# Sheet1.net
KiCad netlist of a schematic drawn in Altium Designer
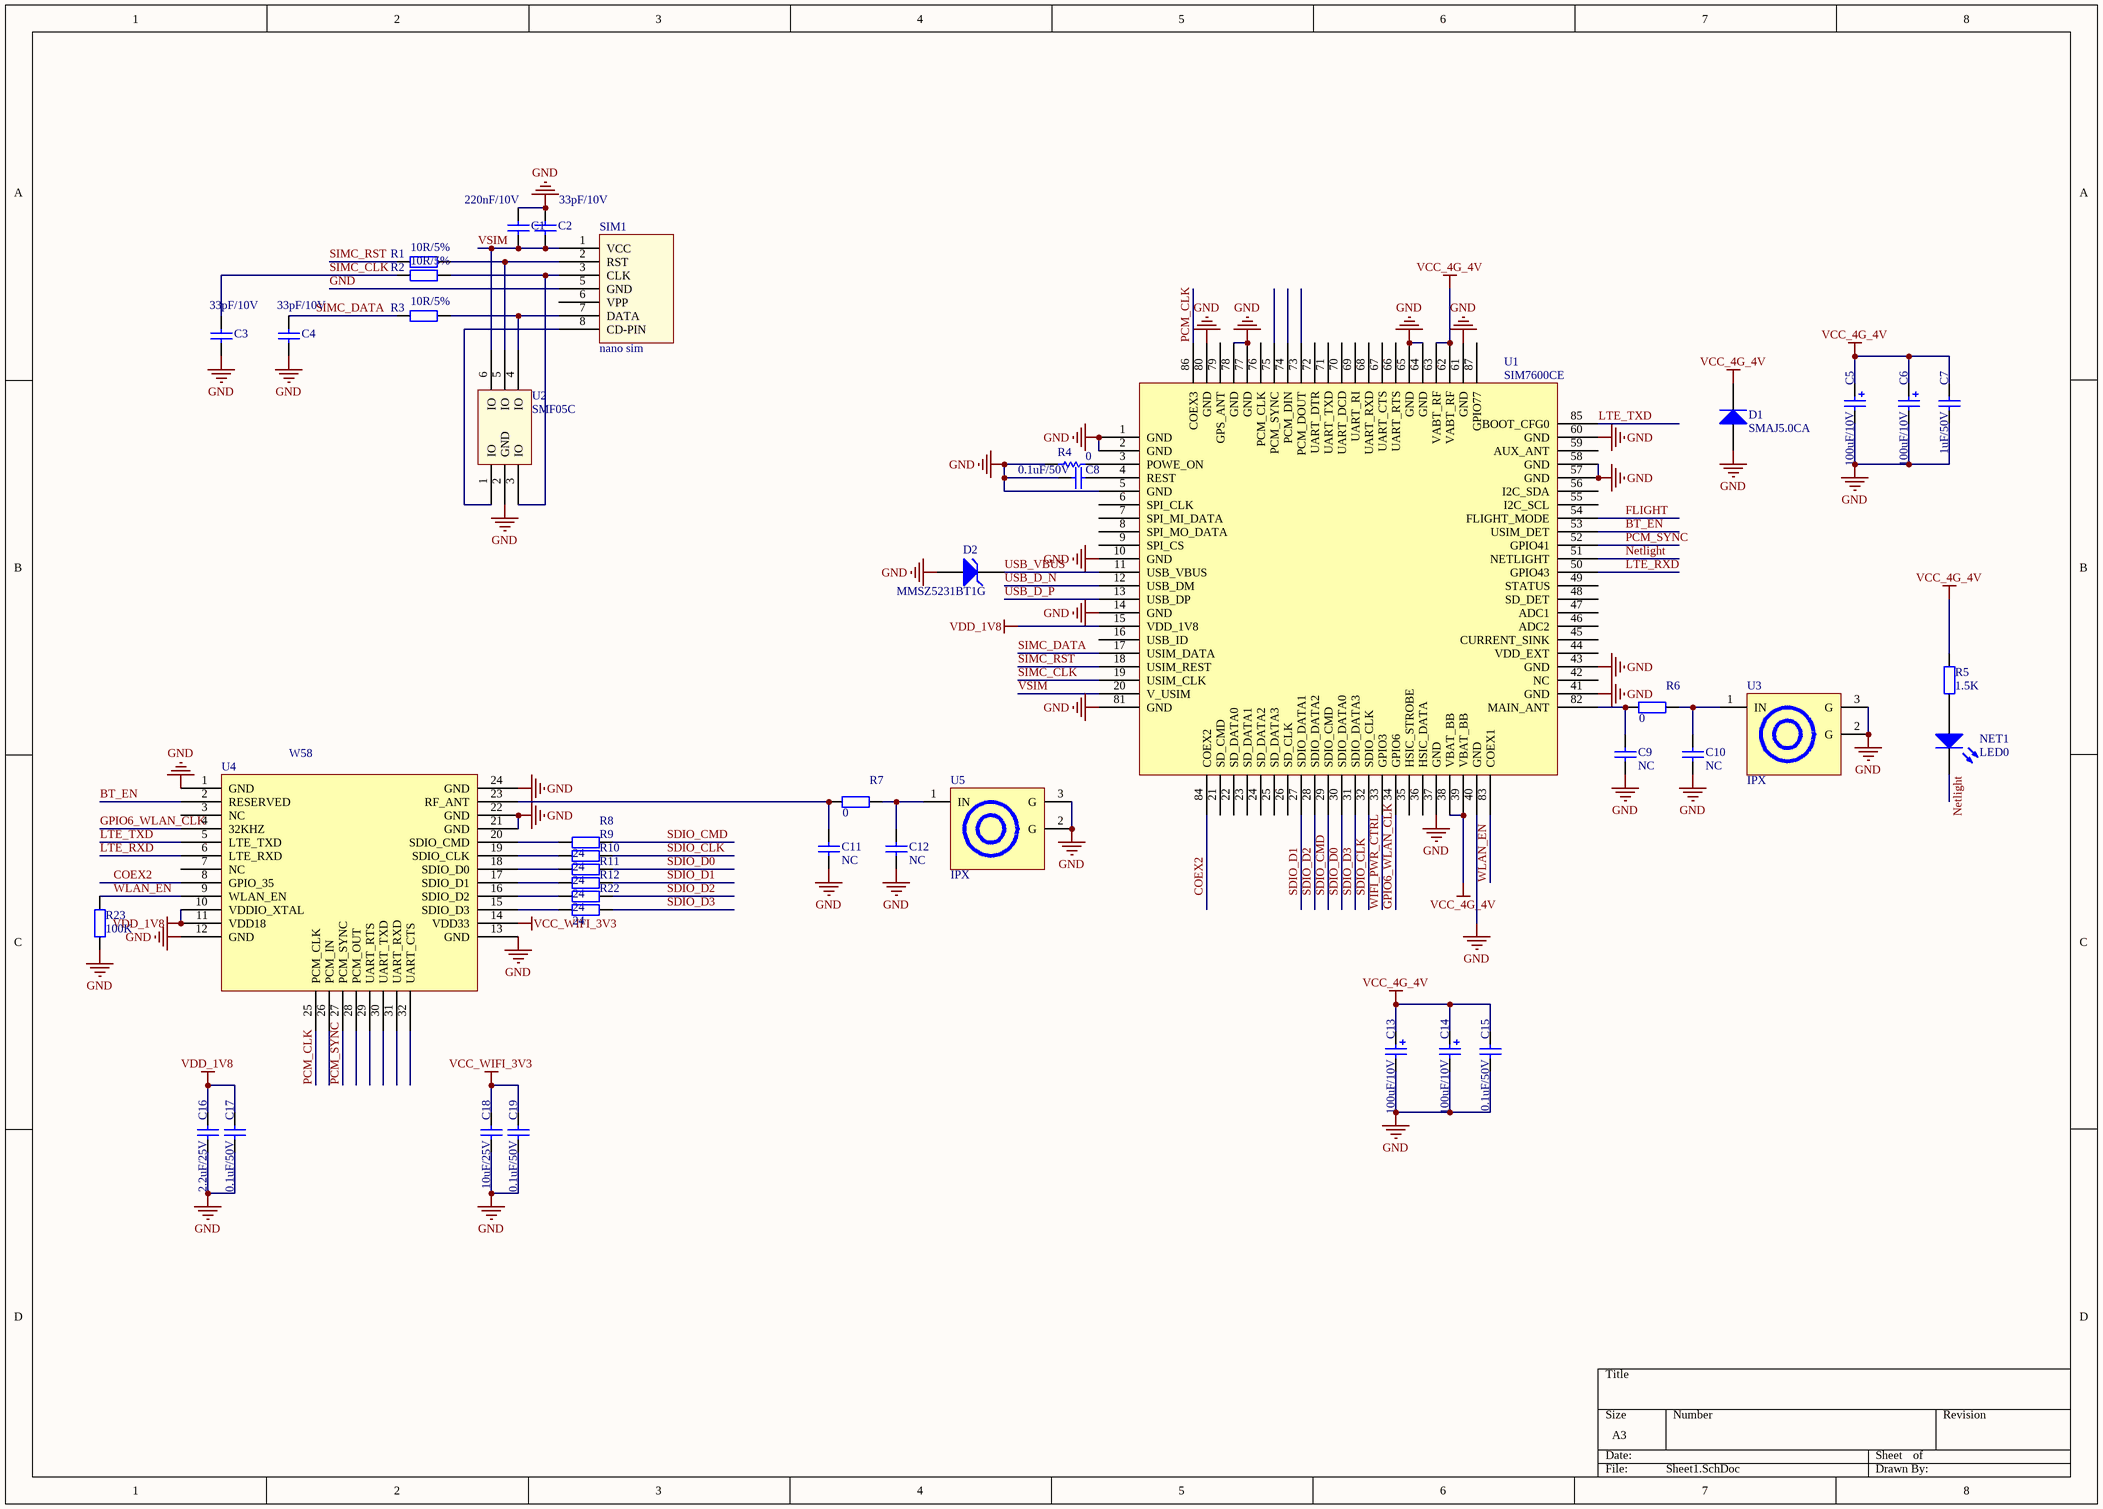
[diagram p0: Sheet1.SchDoc]

(export (version "E")
  (design (tool "Eeschema 10.0.6"))
  (components
    (comp (ref "C1")
      (value "220nF/10V")
      (footprint "C0402")
      (description "Capacitor")
      (fields (field (name "PUBLISHER") "Altium Limited"))
      (libsource (lib "Miscellaneous Devices") (part "Cap"))
    )
    (comp (ref "C2")
      (value "33pF/10V")
      (footprint "C0402")
      (description "Capacitor")
      (fields (field (name "PUBLISHER") "Altium Limited"))
      (libsource (lib "Miscellaneous Devices") (part "Cap"))
    )
    (comp (ref "C3")
      (value "33pF/10V")
      (footprint "C0402")
      (description "Capacitor")
      (fields (field (name "PUBLISHER") "Altium Limited"))
      (libsource (lib "Miscellaneous Devices") (part "Cap"))
    )
    (comp (ref "C4")
      (value "33pF/10V")
      (footprint "C0402")
      (description "Capacitor")
      (fields (field (name "PUBLISHER") "Altium Limited"))
      (libsource (lib "Miscellaneous Devices") (part "Cap"))
    )
    (comp (ref "C5")
      (value "100uF/10V")
      (footprint "3528")
      (description "Polarized Capacitor (Axial)")
      (fields (field (name "PUBLISHER") "Altium Limited"))
      (libsource (lib "Miscellaneous Devices") (part "Cap Pol2"))
    )
    (comp (ref "C6")
      (value "100uF/10V")
      (footprint "3528")
      (description "Polarized Capacitor (Axial)")
      (fields (field (name "PUBLISHER") "Altium Limited"))
      (libsource (lib "Miscellaneous Devices") (part "Cap Pol2"))
    )
    (comp (ref "C7")
      (value "1uF/50V")
      (footprint "0402C")
      (description "Capacitor")
      (fields (field (name "PUBLISHER") "Altium Limited"))
      (libsource (lib "Miscellaneous Devices") (part "Cap"))
    )
    (comp (ref "C8")
      (value "0.1uF/50V")
      (footprint "0402C")
      (description "Capacitor")
      (fields (field (name "PUBLISHER") "Altium Limited"))
      (libsource (lib "Miscellaneous Devices") (part "Cap"))
    )
    (comp (ref "C9")
      (value "NC")
      (footprint "0402C")
      (description "Capacitor")
      (fields (field (name "PUBLISHER") "Altium Limited"))
      (libsource (lib "Miscellaneous Devices") (part "Cap"))
    )
    (comp (ref "C10")
      (value "NC")
      (footprint "0402C")
      (description "Capacitor")
      (fields (field (name "PUBLISHER") "Altium Limited"))
      (libsource (lib "Miscellaneous Devices") (part "Cap"))
    )
    (comp (ref "C11")
      (value "NC")
      (footprint "0402C")
      (description "Capacitor")
      (fields (field (name "PUBLISHER") "Altium Limited"))
      (libsource (lib "Miscellaneous Devices") (part "Cap"))
    )
    (comp (ref "C12")
      (value "NC")
      (footprint "0402C")
      (description "Capacitor")
      (fields (field (name "PUBLISHER") "Altium Limited"))
      (libsource (lib "Miscellaneous Devices") (part "Cap"))
    )
    (comp (ref "C13")
      (value "100uF/10V")
      (footprint "3528")
      (description "Polarized Capacitor (Axial)")
      (fields (field (name "PUBLISHER") "Altium Limited"))
      (libsource (lib "Miscellaneous Devices") (part "Cap Pol2"))
    )
    (comp (ref "C14")
      (value "100uF/10V")
      (footprint "3528")
      (description "Polarized Capacitor (Axial)")
      (fields (field (name "PUBLISHER") "Altium Limited"))
      (libsource (lib "Miscellaneous Devices") (part "Cap Pol2"))
    )
    (comp (ref "C15")
      (value "0.1uF/50V")
      (footprint "0402C")
      (description "Capacitor")
      (fields (field (name "PUBLISHER") "Altium Limited"))
      (libsource (lib "Miscellaneous Devices") (part "Cap"))
    )
    (comp (ref "C16")
      (value "2.2uF/25V")
      (footprint "0402C")
      (description "Capacitor")
      (fields (field (name "PUBLISHER") "Altium Limited"))
      (libsource (lib "Miscellaneous Devices") (part "Cap"))
    )
    (comp (ref "C17")
      (value "0.1uF/50V")
      (footprint "0402C")
      (description "Capacitor")
      (fields (field (name "PUBLISHER") "Altium Limited"))
      (libsource (lib "Miscellaneous Devices") (part "Cap"))
    )
    (comp (ref "C18")
      (value "10uF/25V")
      (footprint "0402C")
      (description "Capacitor")
      (fields (field (name "PUBLISHER") "Altium Limited"))
      (libsource (lib "Miscellaneous Devices") (part "Cap"))
    )
    (comp (ref "C19")
      (value "0.1uF/50V")
      (footprint "0402C")
      (description "Capacitor")
      (fields (field (name "PUBLISHER") "Altium Limited"))
      (libsource (lib "Miscellaneous Devices") (part "Cap"))
    )
    (comp (ref "D1")
      (value "SMAJ5.0CA")
      (footprint "SMA")
      (description "Default Diode")
      (fields (field (name "PUBLISHER") "Altium Limited"))
      (libsource (lib "Miscellaneous Devices") (part "Diode"))
    )
    (comp (ref "D2")
      (value "MMSZ5231BT1G")
      (footprint "SOD123")
      (description "Zener Diode")
      (fields (field (name "PUBLISHER") "Altium Limited"))
      (libsource (lib "Miscellaneous Devices") (part "D Zener"))
    )
    (comp (ref "NET1")
      (value "LED0")
      (footprint "0603LED")
      (description "Typical INFRARED GaAs LED")
      (fields (field (name "PUBLISHER") "Altium Limited"))
      (libsource (lib "Miscellaneous Devices") (part "LED0"))
    )
    (comp (ref "R1")
      (value "10R/5%")
      (footprint "0402R")
      (description "Resistor")
      (fields (field (name "PUBLISHER") "Altium Limited"))
      (libsource (lib "Miscellaneous Devices") (part "Res2"))
    )
    (comp (ref "R2")
      (value "10R/5%")
      (footprint "0402R")
      (description "Resistor")
      (fields (field (name "PUBLISHER") "Altium Limited"))
      (libsource (lib "Miscellaneous Devices") (part "Res2"))
    )
    (comp (ref "R3")
      (value "10R/5%")
      (footprint "0402R")
      (description "Resistor")
      (fields (field (name "PUBLISHER") "Altium Limited"))
      (libsource (lib "Miscellaneous Devices") (part "Res2"))
    )
    (comp (ref "R4")
      (value "0")
      (footprint "0603R")
      (description "Resistor")
      (fields (field (name "PUBLISHER") "Altium Limited"))
      (libsource (lib "Miscellaneous Devices") (part "Res1"))
    )
    (comp (ref "R5")
      (value "1.5K")
      (footprint "0402R")
      (description "Resistor")
      (fields (field (name "PUBLISHER") "Altium Limited"))
      (libsource (lib "") (part "Res2_3"))
    )
    (comp (ref "R6")
      (value "0")
      (footprint "0402R")
      (description "Resistor")
      (fields (field (name "PUBLISHER") "Altium Limited"))
      (libsource (lib "") (part "Res2_2"))
    )
    (comp (ref "R7")
      (value "0")
      (footprint "0402R")
      (description "Resistor")
      (fields (field (name "PUBLISHER") "Altium Limited"))
      (libsource (lib "") (part "Res2_2"))
    )
    (comp (ref "R8")
      (value "24")
      (footprint "0402R")
      (description "Resistor")
      (fields (field (name "PUBLISHER") "Altium Limited"))
      (libsource (lib "") (part "Res2_2"))
    )
    (comp (ref "R9")
      (value "24")
      (footprint "0402R")
      (description "Resistor")
      (fields (field (name "PUBLISHER") "Altium Limited"))
      (libsource (lib "") (part "Res2_2"))
    )
    (comp (ref "R10")
      (value "24")
      (footprint "0402R")
      (description "Resistor")
      (fields (field (name "PUBLISHER") "Altium Limited"))
      (libsource (lib "") (part "Res2_2"))
    )
    (comp (ref "R11")
      (value "24")
      (footprint "0402R")
      (description "Resistor")
      (fields (field (name "PUBLISHER") "Altium Limited"))
      (libsource (lib "") (part "Res2_2"))
    )
    (comp (ref "R12")
      (value "24")
      (footprint "0402R")
      (description "Resistor")
      (fields (field (name "PUBLISHER") "Altium Limited"))
      (libsource (lib "") (part "Res2_2"))
    )
    (comp (ref "R22")
      (value "24")
      (footprint "0402R")
      (description "Resistor")
      (fields (field (name "PUBLISHER") "Altium Limited"))
      (libsource (lib "") (part "Res2_2"))
    )
    (comp (ref "R23")
      (value "100K")
      (footprint "0402R")
      (description "Resistor")
      (fields (field (name "PUBLISHER") "Altium Limited"))
      (libsource (lib "") (part "Res2_1"))
    )
    (comp (ref "SIM1") (value "nano sim") (footprint "Nano SIM") (libsource (lib "lm") (part "nano sim")))
    (comp (ref "U1")
      (value "SIM7600CE")
      (footprint "Pcblib_20110825:SIM7600CE")
      (libsource (lib "DTU_20161116_ZM_V1.1") (part "SIM7600CE"))
    )
    (comp (ref "U2") (value "SMF05C") (footprint "SC70-6L") (libsource (lib "lm") (part "SMF05C")))
    (comp (ref "U3")
      (value "IPX")
      (footprint "ECT8180001581")
      (description "MCU")
      (libsource (lib "MCU") (part "IPX"))
    )
    (comp (ref "U4") (value "W58") (footprint "W58") (libsource (lib "DTU_20161116_ZM_V1.1") (part "W58")))
    (comp (ref "U5")
      (value "IPX")
      (footprint "ECT8180001581")
      (description "MCU")
      (libsource (lib "MCU") (part "IPX"))
    )
  )
  (nets
    (net (code "1") (name "/BT_EN") (class "Default")
      (node (ref "U1") (pin "53") (pinfunction "USIM_DET_53") (pintype "passive"))
      (node (ref "U4") (pin "2") (pinfunction "RESERVED_2") (pintype "passive"))
    )
    (net (code "2") (name "/COEX2") (class "Default")
      (node (ref "U1") (pin "84") (pinfunction "COEX2_84") (pintype "passive"))
      (node (ref "U4") (pin "8") (pinfunction "GPIO_35_8") (pintype "passive"))
    )
    (net (code "3") (name "/FLIGHT") (class "Default")
      (node (ref "U1") (pin "54") (pinfunction "FLIGHT_MODE_54") (pintype "passive"))
    )
    (net (code "4") (name "/GPIO6_WLAN_CLK") (class "Default")
      (node (ref "U1") (pin "34") (pinfunction "GPIO6_34") (pintype "passive"))
      (node (ref "U4") (pin "4") (pinfunction "32KHZ_4") (pintype "passive"))
    )
    (net (code "5") (name "/LTE_RXD") (class "Default")
      (node (ref "U1") (pin "50") (pinfunction "GPIO43_50") (pintype "passive"))
      (node (ref "U4") (pin "6") (pinfunction "LTE_RXD_6") (pintype "passive"))
    )
    (net (code "6") (name "/LTE_TXD") (class "Default")
      (node (ref "U1") (pin "85") (pinfunction "BOOT_CFG0_85") (pintype "passive"))
      (node (ref "U4") (pin "5") (pinfunction "LTE_TXD_5") (pintype "passive"))
    )
    (net (code "7") (name "/Netlight") (class "Default")
      (node (ref "NET1") (pin "2") (pinfunction "K_2") (pintype "passive"))
      (node (ref "U1") (pin "51") (pinfunction "NETLIGHT_51") (pintype "passive"))
    )
    (net (code "8") (name "/PCM_CLK") (class "Default")
      (node (ref "U1") (pin "86") (pinfunction "COEX3_86") (pintype "passive"))
      (node (ref "U4") (pin "25") (pinfunction "PCM_CLK_25") (pintype "passive"))
    )
    (net (code "9") (name "/PCM_SYNC") (class "Default")
      (node (ref "U1") (pin "52") (pinfunction "GPIO41_52") (pintype "passive"))
      (node (ref "U4") (pin "27") (pinfunction "PCM_SYNC_27") (pintype "passive"))
    )
    (net (code "10") (name "/SDIO_CLK") (class "Default")
      (node (ref "R9") (pin "2") (pinfunction "2_2") (pintype "passive"))
      (node (ref "U1") (pin "32") (pinfunction "SDIO_CLK_32") (pintype "passive"))
    )
    (net (code "11") (name "/SDIO_CMD") (class "Default")
      (node (ref "R8") (pin "2") (pinfunction "2_2") (pintype "passive"))
      (node (ref "U1") (pin "29") (pinfunction "SDIO_CMD_29") (pintype "passive"))
    )
    (net (code "12") (name "/SDIO_D0") (class "Default")
      (node (ref "R10") (pin "2") (pinfunction "2_2") (pintype "passive"))
      (node (ref "U1") (pin "30") (pinfunction "SDIO_DATA0_30") (pintype "passive"))
    )
    (net (code "13") (name "/SDIO_D1") (class "Default")
      (node (ref "R11") (pin "2") (pinfunction "2_2") (pintype "passive"))
      (node (ref "U1") (pin "27") (pinfunction "SDIO_DATA1_27") (pintype "passive"))
    )
    (net (code "14") (name "/SDIO_D2") (class "Default")
      (node (ref "R12") (pin "2") (pinfunction "2_2") (pintype "passive"))
      (node (ref "U1") (pin "28") (pinfunction "SDIO_DATA2_28") (pintype "passive"))
    )
    (net (code "15") (name "/SDIO_D3") (class "Default")
      (node (ref "R22") (pin "2") (pinfunction "2_2") (pintype "passive"))
      (node (ref "U1") (pin "31") (pinfunction "SDIO_DATA3_31") (pintype "passive"))
    )
    (net (code "16") (name "/SIMC_CLK") (class "Default")
      (node (ref "C3") (pin "1") (pinfunction "1_1") (pintype "passive"))
      (node (ref "R2") (pin "2") (pinfunction "2_2") (pintype "passive"))
      (node (ref "U1") (pin "19") (pinfunction "USIM_CLK_19") (pintype "passive"))
    )
    (net (code "17") (name "/SIMC_DATA") (class "Default")
      (node (ref "C4") (pin "1") (pinfunction "1_1") (pintype "passive"))
      (node (ref "R3") (pin "2") (pinfunction "2_2") (pintype "passive"))
      (node (ref "U1") (pin "17") (pinfunction "USIM_DATA_17") (pintype "passive"))
    )
    (net (code "18") (name "/SIMC_RST") (class "Default")
      (node (ref "R1") (pin "2") (pinfunction "2_2") (pintype "passive"))
      (node (ref "U1") (pin "18") (pinfunction "USIM_REST_18") (pintype "passive"))
    )
    (net (code "19") (name "/USB_D_N") (class "Default")
      (node (ref "U1") (pin "12") (pinfunction "USB_DM_12") (pintype "passive"))
    )
    (net (code "20") (name "/USB_D_P") (class "Default")
      (node (ref "U1") (pin "13") (pinfunction "USB_DP_13") (pintype "passive"))
    )
    (net (code "21") (name "/USB_VBUS") (class "Default")
      (node (ref "D2") (pin "K") (pinfunction "K_K") (pintype "passive"))
      (node (ref "U1") (pin "11") (pinfunction "USB_VBUS_11") (pintype "passive"))
    )
    (net (code "22") (name "/VSIM") (class "Default")
      (node (ref "C1") (pin "2") (pinfunction "2_2") (pintype "passive"))
      (node (ref "C2") (pin "2") (pinfunction "2_2") (pintype "passive"))
      (node (ref "SIM1") (pin "1") (pinfunction "VCC_1") (pintype "passive"))
      (node (ref "U1") (pin "20") (pinfunction "V_USIM_20") (pintype "passive"))
      (node (ref "U2") (pin "6") (pinfunction "IO_6") (pintype "passive"))
    )
    (net (code "23") (name "/WIFI_PWR_CTRL") (class "Default")
      (node (ref "U1") (pin "33") (pinfunction "GPIO3_33") (pintype "passive"))
    )
    (net (code "24") (name "/WLAN_EN") (class "Default")
      (node (ref "R23") (pin "2") (pinfunction "2_2") (pintype "passive"))
      (node (ref "U1") (pin "83") (pinfunction "COEX1_83") (pintype "passive"))
      (node (ref "U4") (pin "9") (pinfunction "WLAN_EN_9") (pintype "passive"))
    )
    (net (code "25") (name "GND") (class "Default")
      (node (ref "C1") (pin "1") (pinfunction "1_1") (pintype "passive"))
      (node (ref "C10") (pin "1") (pinfunction "1_1") (pintype "passive"))
      (node (ref "C11") (pin "1") (pinfunction "1_1") (pintype "passive"))
      (node (ref "C12") (pin "1") (pinfunction "1_1") (pintype "passive"))
      (node (ref "C13") (pin "2") (pinfunction "2_2") (pintype "passive"))
      (node (ref "C14") (pin "2") (pinfunction "2_2") (pintype "passive"))
      (node (ref "C15") (pin "2") (pinfunction "2_2") (pintype "passive"))
      (node (ref "C16") (pin "2") (pinfunction "2_2") (pintype "passive"))
      (node (ref "C17") (pin "2") (pinfunction "2_2") (pintype "passive"))
      (node (ref "C18") (pin "2") (pinfunction "2_2") (pintype "passive"))
      (node (ref "C19") (pin "2") (pinfunction "2_2") (pintype "passive"))
      (node (ref "C2") (pin "1") (pinfunction "1_1") (pintype "passive"))
      (node (ref "C3") (pin "2") (pinfunction "2_2") (pintype "passive"))
      (node (ref "C4") (pin "2") (pinfunction "2_2") (pintype "passive"))
      (node (ref "C5") (pin "2") (pinfunction "2_2") (pintype "passive"))
      (node (ref "C6") (pin "2") (pinfunction "2_2") (pintype "passive"))
      (node (ref "C7") (pin "2") (pinfunction "2_2") (pintype "passive"))
      (node (ref "C8") (pin "1") (pinfunction "1_1") (pintype "passive"))
      (node (ref "C9") (pin "1") (pinfunction "1_1") (pintype "passive"))
      (node (ref "D1") (pin "1") (pinfunction "A_1") (pintype "passive"))
      (node (ref "D2") (pin "A") (pinfunction "A_A") (pintype "passive"))
      (node (ref "R23") (pin "1") (pinfunction "1_1") (pintype "passive"))
      (node (ref "R4") (pin "1") (pinfunction "1_1") (pintype "passive"))
      (node (ref "SIM1") (pin "5") (pinfunction "GND_5") (pintype "passive"))
      (node (ref "U1") (pin "1") (pinfunction "GND_1") (pintype "passive"))
      (node (ref "U1") (pin "10") (pinfunction "GND_10") (pintype "passive"))
      (node (ref "U1") (pin "14") (pinfunction "GND_14") (pintype "passive"))
      (node (ref "U1") (pin "2") (pinfunction "GND_2") (pintype "passive"))
      (node (ref "U1") (pin "37") (pinfunction "GND_37") (pintype "passive"))
      (node (ref "U1") (pin "40") (pinfunction "GND_40") (pintype "passive"))
      (node (ref "U1") (pin "41") (pinfunction "GND_41") (pintype "passive"))
      (node (ref "U1") (pin "43") (pinfunction "GND_43") (pintype "passive"))
      (node (ref "U1") (pin "5") (pinfunction "GND_5") (pintype "passive"))
      (node (ref "U1") (pin "57") (pinfunction "GND_57") (pintype "passive"))
      (node (ref "U1") (pin "58") (pinfunction "GND_58") (pintype "passive"))
      (node (ref "U1") (pin "60") (pinfunction "GND_60") (pintype "passive"))
      (node (ref "U1") (pin "61") (pinfunction "GND_61") (pintype "passive"))
      (node (ref "U1") (pin "64") (pinfunction "GND_64") (pintype "passive"))
      (node (ref "U1") (pin "65") (pinfunction "GND_65") (pintype "passive"))
      (node (ref "U1") (pin "77") (pinfunction "GND_77") (pintype "passive"))
      (node (ref "U1") (pin "78") (pinfunction "GND_78") (pintype "passive"))
      (node (ref "U1") (pin "80") (pinfunction "GND_80") (pintype "passive"))
      (node (ref "U1") (pin "81") (pinfunction "GND_81") (pintype "passive"))
      (node (ref "U2") (pin "2") (pinfunction "GND_2") (pintype "passive"))
      (node (ref "U3") (pin "2") (pinfunction "G_2") (pintype "passive"))
      (node (ref "U3") (pin "3") (pinfunction "G_3") (pintype "passive"))
      (node (ref "U4") (pin "1") (pinfunction "GND_1") (pintype "passive"))
      (node (ref "U4") (pin "12") (pinfunction "GND_12") (pintype "passive"))
      (node (ref "U4") (pin "13") (pinfunction "GND_13") (pintype "passive"))
      (node (ref "U4") (pin "21") (pinfunction "GND_21") (pintype "passive"))
      (node (ref "U4") (pin "22") (pinfunction "GND_22") (pintype "passive"))
      (node (ref "U4") (pin "24") (pinfunction "GND_24") (pintype "passive"))
      (node (ref "U5") (pin "2") (pinfunction "G_2") (pintype "passive"))
      (node (ref "U5") (pin "3") (pinfunction "G_3") (pintype "passive"))
    )
    (net (code "26") (name "Net-(NET1-A)") (class "Default")
      (node (ref "NET1") (pin "1") (pinfunction "A_1") (pintype "passive"))
      (node (ref "R5") (pin "2") (pinfunction "2_2") (pintype "passive"))
    )
    (net (code "27") (name "Net-(SIM1-CD-PIN)") (class "Default")
      (node (ref "SIM1") (pin "8") (pinfunction "CD-PIN_8") (pintype "passive"))
      (node (ref "U2") (pin "1") (pinfunction "IO_1") (pintype "passive"))
    )
    (net (code "28") (name "Net-(SIM1-CLK)") (class "Default")
      (node (ref "R2") (pin "1") (pinfunction "1_1") (pintype "passive"))
      (node (ref "SIM1") (pin "3") (pinfunction "CLK_3") (pintype "passive"))
      (node (ref "U2") (pin "3") (pinfunction "IO_3") (pintype "passive"))
    )
    (net (code "29") (name "Net-(SIM1-DATA)") (class "Default")
      (node (ref "R3") (pin "1") (pinfunction "1_1") (pintype "passive"))
      (node (ref "SIM1") (pin "7") (pinfunction "DATA_7") (pintype "passive"))
      (node (ref "U2") (pin "4") (pinfunction "IO_4") (pintype "passive"))
    )
    (net (code "30") (name "Net-(SIM1-RST)") (class "Default")
      (node (ref "R1") (pin "1") (pinfunction "1_1") (pintype "passive"))
      (node (ref "SIM1") (pin "2") (pinfunction "RST_2") (pintype "passive"))
      (node (ref "U2") (pin "5") (pinfunction "IO_5") (pintype "passive"))
    )
    (net (code "31") (name "Net-(U1-MAIN_ANT)") (class "Default")
      (node (ref "C9") (pin "2") (pinfunction "2_2") (pintype "passive"))
      (node (ref "R6") (pin "1") (pinfunction "1_1") (pintype "passive"))
      (node (ref "U1") (pin "82") (pinfunction "MAIN_ANT_82") (pintype "passive"))
    )
    (net (code "32") (name "Net-(U1-POWE_ON)") (class "Default")
      (node (ref "R4") (pin "2") (pinfunction "2_2") (pintype "passive"))
      (node (ref "U1") (pin "3") (pinfunction "POWE_ON_3") (pintype "passive"))
    )
    (net (code "33") (name "Net-(U1-REST)") (class "Default")
      (node (ref "C8") (pin "2") (pinfunction "2_2") (pintype "passive"))
      (node (ref "U1") (pin "4") (pinfunction "REST_4") (pintype "passive"))
    )
    (net (code "34") (name "Net-(U3-IN)") (class "Default")
      (node (ref "C10") (pin "2") (pinfunction "2_2") (pintype "passive"))
      (node (ref "R6") (pin "2") (pinfunction "2_2") (pintype "passive"))
      (node (ref "U3") (pin "1") (pinfunction "IN_1") (pintype "passive"))
    )
    (net (code "35") (name "Net-(U4-RF_ANT)") (class "Default")
      (node (ref "C11") (pin "2") (pinfunction "2_2") (pintype "passive"))
      (node (ref "R7") (pin "1") (pinfunction "1_1") (pintype "passive"))
      (node (ref "U4") (pin "23") (pinfunction "RF_ANT_23") (pintype "passive"))
    )
    (net (code "36") (name "Net-(U4-SDIO_CLK)") (class "Default")
      (node (ref "R9") (pin "1") (pinfunction "1_1") (pintype "passive"))
      (node (ref "U4") (pin "19") (pinfunction "SDIO_CLK_19") (pintype "passive"))
    )
    (net (code "37") (name "Net-(U4-SDIO_CMD)") (class "Default")
      (node (ref "R8") (pin "1") (pinfunction "1_1") (pintype "passive"))
      (node (ref "U4") (pin "20") (pinfunction "SDIO_CMD_20") (pintype "passive"))
    )
    (net (code "38") (name "Net-(U4-SDIO_D0)") (class "Default")
      (node (ref "R10") (pin "1") (pinfunction "1_1") (pintype "passive"))
      (node (ref "U4") (pin "18") (pinfunction "SDIO_D0_18") (pintype "passive"))
    )
    (net (code "39") (name "Net-(U4-SDIO_D1)") (class "Default")
      (node (ref "R11") (pin "1") (pinfunction "1_1") (pintype "passive"))
      (node (ref "U4") (pin "17") (pinfunction "SDIO_D1_17") (pintype "passive"))
    )
    (net (code "40") (name "Net-(U4-SDIO_D2)") (class "Default")
      (node (ref "R12") (pin "1") (pinfunction "1_1") (pintype "passive"))
      (node (ref "U4") (pin "16") (pinfunction "SDIO_D2_16") (pintype "passive"))
    )
    (net (code "41") (name "Net-(U4-SDIO_D3)") (class "Default")
      (node (ref "R22") (pin "1") (pinfunction "1_1") (pintype "passive"))
      (node (ref "U4") (pin "15") (pinfunction "SDIO_D3_15") (pintype "passive"))
    )
    (net (code "42") (name "Net-(U5-IN)") (class "Default")
      (node (ref "C12") (pin "2") (pinfunction "2_2") (pintype "passive"))
      (node (ref "R7") (pin "2") (pinfunction "2_2") (pintype "passive"))
      (node (ref "U5") (pin "1") (pinfunction "IN_1") (pintype "passive"))
    )
    (net (code "43") (name "VCC_4G_4V") (class "Default")
      (node (ref "C13") (pin "1") (pinfunction "1_1") (pintype "passive"))
      (node (ref "C14") (pin "1") (pinfunction "1_1") (pintype "passive"))
      (node (ref "C15") (pin "1") (pinfunction "1_1") (pintype "passive"))
      (node (ref "C5") (pin "1") (pinfunction "1_1") (pintype "passive"))
      (node (ref "C6") (pin "1") (pinfunction "1_1") (pintype "passive"))
      (node (ref "C7") (pin "1") (pinfunction "1_1") (pintype "passive"))
      (node (ref "D1") (pin "2") (pinfunction "K_2") (pintype "passive"))
      (node (ref "R5") (pin "1") (pinfunction "1_1") (pintype "passive"))
      (node (ref "U1") (pin "38") (pinfunction "VBAT_BB_38") (pintype "passive"))
      (node (ref "U1") (pin "39") (pinfunction "VBAT_BB_39") (pintype "passive"))
      (node (ref "U1") (pin "62") (pinfunction "VABT_RF_62") (pintype "passive"))
      (node (ref "U1") (pin "63") (pinfunction "VABT_RF_63") (pintype "passive"))
    )
    (net (code "44") (name "VCC_WIFI_3V3") (class "Default")
      (node (ref "C18") (pin "1") (pinfunction "1_1") (pintype "passive"))
      (node (ref "C19") (pin "1") (pinfunction "1_1") (pintype "passive"))
      (node (ref "U4") (pin "14") (pinfunction "VDD33_14") (pintype "passive"))
    )
    (net (code "45") (name "VDD_1V8") (class "Default")
      (node (ref "C16") (pin "1") (pinfunction "1_1") (pintype "passive"))
      (node (ref "C17") (pin "1") (pinfunction "1_1") (pintype "passive"))
      (node (ref "U1") (pin "15") (pinfunction "VDD_1V8_15") (pintype "passive"))
      (node (ref "U4") (pin "10") (pinfunction "VDDIO_XTAL_10") (pintype "passive"))
      (node (ref "U4") (pin "11") (pinfunction "VDD18_11") (pintype "passive"))
    )
    (net (code "46") (name "unconnected-(SIM1-VPP-Pad6)") (class "Default")
      (node (ref "SIM1") (pin "6") (pinfunction "VPP_6") (pintype "passive"))
    )
    (net (code "47") (name "unconnected-(U1-ADC1-Pad47)") (class "Default")
      (node (ref "U1") (pin "47") (pinfunction "ADC1_47") (pintype "passive"))
    )
    (net (code "48") (name "unconnected-(U1-ADC2-Pad46)") (class "Default")
      (node (ref "U1") (pin "46") (pinfunction "ADC2_46") (pintype "passive"))
    )
    (net (code "49") (name "unconnected-(U1-AUX_ANT-Pad59)") (class "Default")
      (node (ref "U1") (pin "59") (pinfunction "AUX_ANT_59") (pintype "passive"))
    )
    (net (code "50") (name "unconnected-(U1-CURRENT_SINK-Pad45)") (class "Default")
      (node (ref "U1") (pin "45") (pinfunction "CURRENT_SINK_45") (pintype "passive"))
    )
    (net (code "51") (name "unconnected-(U1-GPIO77-Pad87)") (class "Default")
      (node (ref "U1") (pin "87") (pinfunction "GPIO77_87") (pintype "passive"))
    )
    (net (code "52") (name "unconnected-(U1-GPS_ANT-Pad79)") (class "Default")
      (node (ref "U1") (pin "79") (pinfunction "GPS_ANT_79") (pintype "passive"))
    )
    (net (code "53") (name "unconnected-(U1-HSIC_DATA-Pad36)") (class "Default")
      (node (ref "U1") (pin "36") (pinfunction "HSIC_DATA_36") (pintype "passive"))
    )
    (net (code "54") (name "unconnected-(U1-HSIC_STROBE-Pad35)") (class "Default")
      (node (ref "U1") (pin "35") (pinfunction "HSIC_STROBE_35") (pintype "passive"))
    )
    (net (code "55") (name "unconnected-(U1-I2C_SCL-Pad55)") (class "Default")
      (node (ref "U1") (pin "55") (pinfunction "I2C_SCL_55") (pintype "passive"))
    )
    (net (code "56") (name "unconnected-(U1-I2C_SDA-Pad56)") (class "Default")
      (node (ref "U1") (pin "56") (pinfunction "I2C_SDA_56") (pintype "passive"))
    )
    (net (code "57") (name "unconnected-(U1-NC-Pad42)") (class "Default")
      (node (ref "U1") (pin "42") (pinfunction "NC_42") (pintype "passive"))
    )
    (net (code "58") (name "unconnected-(U1-PCM_CLK-Pad76)") (class "Default")
      (node (ref "U1") (pin "76") (pinfunction "PCM_CLK_76") (pintype "passive"))
    )
    (net (code "59") (name "unconnected-(U1-PCM_DIN-Pad74)") (class "Default")
      (node (ref "U1") (pin "74") (pinfunction "PCM_DIN_74") (pintype "passive"))
    )
    (net (code "60") (name "unconnected-(U1-PCM_DOUT-Pad73)") (class "Default")
      (node (ref "U1") (pin "73") (pinfunction "PCM_DOUT_73") (pintype "passive"))
    )
    (net (code "61") (name "unconnected-(U1-PCM_SYNC-Pad75)") (class "Default")
      (node (ref "U1") (pin "75") (pinfunction "PCM_SYNC_75") (pintype "passive"))
    )
    (net (code "62") (name "unconnected-(U1-SD_CLK-Pad26)") (class "Default")
      (node (ref "U1") (pin "26") (pinfunction "SD_CLK_26") (pintype "passive"))
    )
    (net (code "63") (name "unconnected-(U1-SD_CMD-Pad21)") (class "Default")
      (node (ref "U1") (pin "21") (pinfunction "SD_CMD_21") (pintype "passive"))
    )
    (net (code "64") (name "unconnected-(U1-SD_DATA0-Pad22)") (class "Default")
      (node (ref "U1") (pin "22") (pinfunction "SD_DATA0_22") (pintype "passive"))
    )
    (net (code "65") (name "unconnected-(U1-SD_DATA1-Pad23)") (class "Default")
      (node (ref "U1") (pin "23") (pinfunction "SD_DATA1_23") (pintype "passive"))
    )
    (net (code "66") (name "unconnected-(U1-SD_DATA2-Pad24)") (class "Default")
      (node (ref "U1") (pin "24") (pinfunction "SD_DATA2_24") (pintype "passive"))
    )
    (net (code "67") (name "unconnected-(U1-SD_DATA3-Pad25)") (class "Default")
      (node (ref "U1") (pin "25") (pinfunction "SD_DATA3_25") (pintype "passive"))
    )
    (net (code "68") (name "unconnected-(U1-SD_DET-Pad48)") (class "Default")
      (node (ref "U1") (pin "48") (pinfunction "SD_DET_48") (pintype "passive"))
    )
    (net (code "69") (name "unconnected-(U1-SPI_CLK-Pad6)") (class "Default")
      (node (ref "U1") (pin "6") (pinfunction "SPI_CLK_6") (pintype "passive"))
    )
    (net (code "70") (name "unconnected-(U1-SPI_CS-Pad9)") (class "Default")
      (node (ref "U1") (pin "9") (pinfunction "SPI_CS_9") (pintype "passive"))
    )
    (net (code "71") (name "unconnected-(U1-SPI_MI_DATA-Pad7)") (class "Default")
      (node (ref "U1") (pin "7") (pinfunction "SPI_MI_DATA_7") (pintype "passive"))
    )
    (net (code "72") (name "unconnected-(U1-SPI_MO_DATA-Pad8)") (class "Default")
      (node (ref "U1") (pin "8") (pinfunction "SPI_MO_DATA_8") (pintype "passive"))
    )
    (net (code "73") (name "unconnected-(U1-STATUS-Pad49)") (class "Default")
      (node (ref "U1") (pin "49") (pinfunction "STATUS_49") (pintype "passive"))
    )
    (net (code "74") (name "unconnected-(U1-UART_CTS-Pad67)") (class "Default")
      (node (ref "U1") (pin "67") (pinfunction "UART_CTS_67") (pintype "passive"))
    )
    (net (code "75") (name "unconnected-(U1-UART_DCD-Pad70)") (class "Default")
      (node (ref "U1") (pin "70") (pinfunction "UART_DCD_70") (pintype "passive"))
    )
    (net (code "76") (name "unconnected-(U1-UART_DTR-Pad72)") (class "Default")
      (node (ref "U1") (pin "72") (pinfunction "UART_DTR_72") (pintype "passive"))
    )
    (net (code "77") (name "unconnected-(U1-UART_RI-Pad69)") (class "Default")
      (node (ref "U1") (pin "69") (pinfunction "UART_RI_69") (pintype "passive"))
    )
    (net (code "78") (name "unconnected-(U1-UART_RTS-Pad66)") (class "Default")
      (node (ref "U1") (pin "66") (pinfunction "UART_RTS_66") (pintype "passive"))
    )
    (net (code "79") (name "unconnected-(U1-UART_RXD-Pad68)") (class "Default")
      (node (ref "U1") (pin "68") (pinfunction "UART_RXD_68") (pintype "passive"))
    )
    (net (code "80") (name "unconnected-(U1-UART_TXD-Pad71)") (class "Default")
      (node (ref "U1") (pin "71") (pinfunction "UART_TXD_71") (pintype "passive"))
    )
    (net (code "81") (name "unconnected-(U1-USB_ID-Pad16)") (class "Default")
      (node (ref "U1") (pin "16") (pinfunction "USB_ID_16") (pintype "passive"))
    )
    (net (code "82") (name "unconnected-(U1-VDD_EXT-Pad44)") (class "Default")
      (node (ref "U1") (pin "44") (pinfunction "VDD_EXT_44") (pintype "passive"))
    )
    (net (code "83") (name "unconnected-(U4-NC-Pad3)") (class "Default")
      (node (ref "U4") (pin "3") (pinfunction "NC_3") (pintype "passive"))
    )
    (net (code "84") (name "unconnected-(U4-NC-Pad7)") (class "Default")
      (node (ref "U4") (pin "7") (pinfunction "NC_7") (pintype "passive"))
    )
    (net (code "85") (name "unconnected-(U4-PCM_IN-Pad26)") (class "Default")
      (node (ref "U4") (pin "26") (pinfunction "PCM_IN_26") (pintype "passive"))
    )
    (net (code "86") (name "unconnected-(U4-PCM_OUT-Pad28)") (class "Default")
      (node (ref "U4") (pin "28") (pinfunction "PCM_OUT_28") (pintype "passive"))
    )
    (net (code "87") (name "unconnected-(U4-UART_CTS-Pad32)") (class "Default")
      (node (ref "U4") (pin "32") (pinfunction "UART_CTS_32") (pintype "passive"))
    )
    (net (code "88") (name "unconnected-(U4-UART_RTS-Pad29)") (class "Default")
      (node (ref "U4") (pin "29") (pinfunction "UART_RTS_29") (pintype "passive"))
    )
    (net (code "89") (name "unconnected-(U4-UART_RXD-Pad31)") (class "Default")
      (node (ref "U4") (pin "31") (pinfunction "UART_RXD_31") (pintype "passive"))
    )
    (net (code "90") (name "unconnected-(U4-UART_TXD-Pad30)") (class "Default")
      (node (ref "U4") (pin "30") (pinfunction "UART_TXD_30") (pintype "passive"))
    )
  )
)
